# Power.net
KiCad netlist of a schematic drawn in Altium Designer
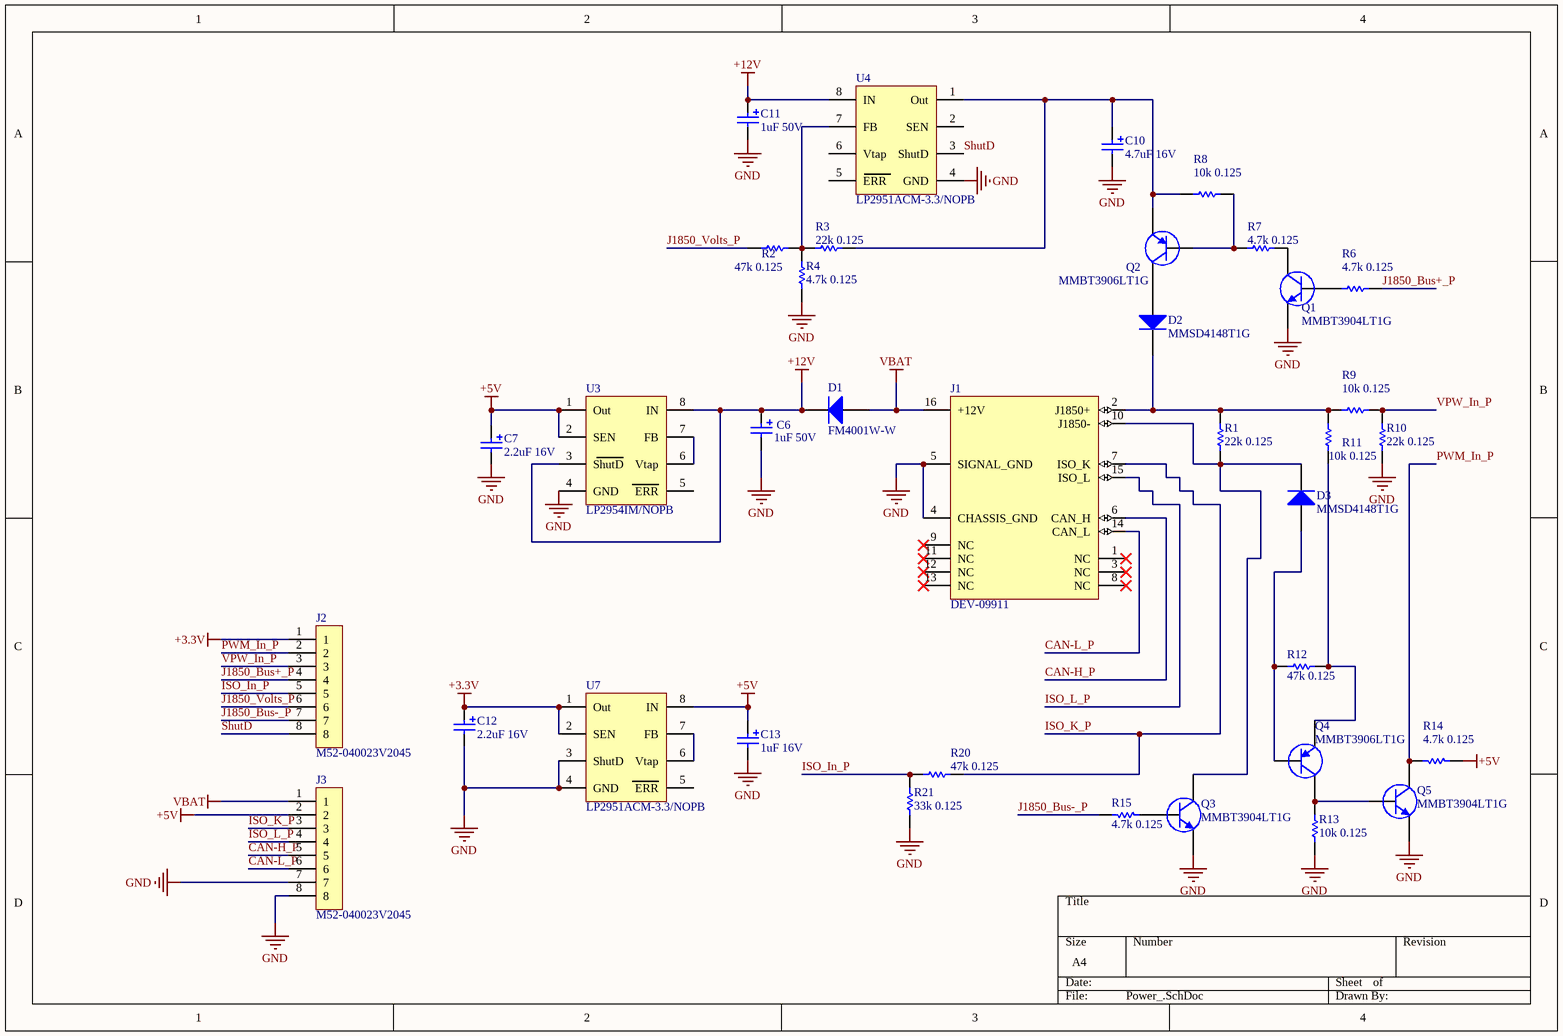
[diagram p0: Power_.SchDoc]

(export (version "E")
  (design (tool "Eeschema 10.0.6"))
  (components
    (comp (ref "C6")
      (value "1uF 50V")
      (footprint "C1005")
      (description "Surface-Mount Electrolitic Tantalum Capacitor, 1uF, 20% Tolerance, 1005 Size, 50V")
      (fields (field (name "PUBLISHER") "Altium Limited"))
      (libsource (lib "OBDII-components") (part "298D105X0050P2T"))
    )
    (comp (ref "C7")
      (value "2.2uF 16V")
      (footprint "C0603")
      (description "Surface-Mount Electrolitic Tantalum Capacitor, 2.2uF, 10% Tolerance, 0603 Size, 16V")
      (fields (field (name "PUBLISHER") "Altium Limited"))
      (libsource (lib "OBDII-components") (part "298D225X0016M2T"))
    )
    (comp (ref "C10")
      (value "4.7uF 16V")
      (footprint "C1005")
      (description "Surface-Mount Electrolitic Tantalum Capacitor, 4.7uF, 20% Tolerance, 1005 Size, 16V")
      (fields (field (name "PUBLISHER") "Altium Limited"))
      (libsource (lib "OBDII-components") (part "298D475X0016P2T"))
    )
    (comp (ref "C11")
      (value "1uF 50V")
      (footprint "C1005")
      (description "Surface-Mount Electrolitic Tantalum Capacitor, 1uF, 20% Tolerance, 1005 Size, 50V")
      (fields (field (name "PUBLISHER") "Altium Limited"))
      (libsource (lib "OBDII-components") (part "298D105X0050P2T"))
    )
    (comp (ref "C12")
      (value "2.2uF 16V")
      (footprint "C0603")
      (description "Surface-Mount Electrolitic Tantalum Capacitor, 2.2uF, 10% Tolerance, 0603 Size, 16V")
      (fields (field (name "PUBLISHER") "Altium Limited"))
      (libsource (lib "OBDII-components") (part "298D225X0016M2T"))
    )
    (comp (ref "C13")
      (value "1uF 16V")
      (footprint "C0603")
      (description "Surface-Mount Electrolitic Tantalum Capacitor, 1uF, 10% Tolerance, 0603 Size, 16V")
      (fields (field (name "PUBLISHER") "Altium Limited"))
      (libsource (lib "OBDII-components") (part "298D105X9016M2T"))
    )
    (comp (ref "D1")
      (value "FM4001W-W")
      (footprint "SMA,2.8mm")
      (description "1 Amp 50V  Rectifier")
      (libsource (lib "OBDII-components") (part "FM4001W-W"))
    )
    (comp (ref "D2")
      (value "MMSD4148T1G")
      (footprint "SOD123")
      (description "High Conductance Fast Diode")
      (fields
        (field (name "MANUFACTURER") "OnSemi")
        (field (name "PUBLISHER") "Vanteon")
        (field (name "APPROVED") "M. Jablonski")
      )
      (libsource (lib "OBDII-components") (part "MMSD4148T1G"))
    )
    (comp (ref "D3")
      (value "MMSD4148T1G")
      (footprint "SOD123")
      (description "High Conductance Fast Diode")
      (fields
        (field (name "MANUFACTURER") "OnSemi")
        (field (name "PUBLISHER") "Vanteon")
        (field (name "APPROVED") "M. Jablonski")
      )
      (libsource (lib "OBDII-components") (part "MMSD4148T1G"))
    )
    (comp (ref "J1")
      (value "DEV-09911")
      (footprint "DEV-09911 - II")
      (description "OBD-II Connector")
      (fields (field (name "MANUFACTURER") "SparkFun Electronics"))
      (libsource (lib "OBDII-components") (part "OBDII_DEV-09911"))
    )
    (comp (ref "J2")
      (value "M52-040023V2045")
      (footprint "M52-040023V2045")
      (description "CONN HEADER .050\" 20POS PCB GOLD")
      (fields (field (name "MANUFACTURER") "Harwin"))
      (libsource (lib "OBDII-components") (part "M52-040023V2045"))
    )
    (comp (ref "J3")
      (value "M52-040023V2045")
      (footprint "M52-040023V2045")
      (description "CONN HEADER .050\" 20POS PCB GOLD")
      (fields (field (name "MANUFACTURER") "Harwin"))
      (libsource (lib "OBDII-components") (part "M52-040023V2045"))
    )
    (comp (ref "Q1")
      (value "MMBT3904LT1G")
      (footprint "SOT23")
      (description "NPN 3904 General Purpose Amplifier")
      (fields
        (field (name "MANUFACTURER") "ON Semiconductor")
        (field (name "PUBLISHER") "Vanteon")
        (field (name "APPROVED") "Yes by Implemenation")
      )
      (libsource (lib "OBDII-components") (part "MMBT3904LT1G"))
    )
    (comp (ref "Q2")
      (value "MMBT3906LT1G")
      (footprint "SOT23")
      (description "PNP 3906 General Purpose Amplifier")
      (fields
        (field (name "MANUFACTURER") "ON Semiconductor")
        (field (name "PUBLISHER") "Vanteon")
        (field (name "APPROVED") "Yes by Implemenation")
      )
      (libsource (lib "OBDII-components") (part "MMBT3906LT1G"))
    )
    (comp (ref "Q3")
      (value "MMBT3904LT1G")
      (footprint "SOT23")
      (description "NPN 3904 General Purpose Amplifier")
      (fields
        (field (name "MANUFACTURER") "ON Semiconductor")
        (field (name "PUBLISHER") "Vanteon")
        (field (name "APPROVED") "Yes by Implemenation")
      )
      (libsource (lib "OBDII-components") (part "MMBT3904LT1G"))
    )
    (comp (ref "Q4")
      (value "MMBT3906LT1G")
      (footprint "SOT23")
      (description "PNP 3906 General Purpose Amplifier")
      (fields
        (field (name "MANUFACTURER") "ON Semiconductor")
        (field (name "PUBLISHER") "Vanteon")
        (field (name "APPROVED") "Yes by Implemenation")
      )
      (libsource (lib "OBDII-components") (part "MMBT3906LT1G"))
    )
    (comp (ref "Q5")
      (value "MMBT3904LT1G")
      (footprint "SOT23")
      (description "NPN 3904 General Purpose Amplifier")
      (fields
        (field (name "MANUFACTURER") "ON Semiconductor")
        (field (name "PUBLISHER") "Vanteon")
        (field (name "APPROVED") "Yes by Implemenation")
      )
      (libsource (lib "OBDII-components") (part "MMBT3904LT1G"))
    )
    (comp (ref "R1")
      (value "22k 0.125")
      (footprint "ERA-0805")
      (description "Rectangular Thick Film Chip Resistor, 22 kOhm, 0.1% Tolerance, 0805 Size, 0.125 W")
      (libsource (lib "OBDII-components") (part "ERA-6AEB223V"))
    )
    (comp (ref "R2")
      (value "47k 0.125")
      (footprint "ERA-0805")
      (description "Rectangular Thick Film Chip Resistor, 47 kOhm, 0.1% Tolerance, 0805 Size, 0.125 W")
      (libsource (lib "OBDII-components") (part "ERA-6AEB473V"))
    )
    (comp (ref "R3")
      (value "22k 0.125")
      (footprint "ERA-0805")
      (description "Rectangular Thick Film Chip Resistor, 22 kOhm, 0.1% Tolerance, 0805 Size, 0.125 W")
      (libsource (lib "OBDII-components") (part "ERA-6AEB223V"))
    )
    (comp (ref "R4")
      (value "4.7k 0.125")
      (footprint "ERA-0805")
      (description "Rectangular Thick Film Chip Resistor, 4.7 kOhm, 0.1% Tolerance, 0805 Size, 0.125 W")
      (libsource (lib "OBDII-components") (part "ERA-6AEB472V"))
    )
    (comp (ref "R6")
      (value "4.7k 0.125")
      (footprint "ERA-0805")
      (description "Rectangular Thick Film Chip Resistor, 4.7 kOhm, 0.1% Tolerance, 0805 Size, 0.125 W")
      (libsource (lib "OBDII-components") (part "ERA-6AEB472V"))
    )
    (comp (ref "R7")
      (value "4.7k 0.125")
      (footprint "ERA-0805")
      (description "Rectangular Thick Film Chip Resistor, 4.7 kOhm, 0.1% Tolerance, 0805 Size, 0.125 W")
      (libsource (lib "OBDII-components") (part "ERA-6AEB472V"))
    )
    (comp (ref "R8")
      (value "10k 0.125")
      (footprint "ERA-0805")
      (description "Rectangular Thick Film Chip Resistor, 10 kOhm, 0.1% Tolerance, 0805 Size, 0.125 W")
      (libsource (lib "OBDII-components") (part "ERA-6AEB103V"))
    )
    (comp (ref "R9")
      (value "10k 0.125")
      (footprint "ERA-0805")
      (description "Rectangular Thick Film Chip Resistor, 10 kOhm, 0.1% Tolerance, 0805 Size, 0.125 W")
      (libsource (lib "OBDII-components") (part "ERA-6AEB103V"))
    )
    (comp (ref "R10")
      (value "22k 0.125")
      (footprint "ERA-0805")
      (description "Rectangular Thick Film Chip Resistor, 22 kOhm, 0.1% Tolerance, 0805 Size, 0.125 W")
      (libsource (lib "OBDII-components") (part "ERA-6AEB223V"))
    )
    (comp (ref "R11")
      (value "10k 0.125")
      (footprint "ERA-0805")
      (description "Rectangular Thick Film Chip Resistor, 10 kOhm, 0.1% Tolerance, 0805 Size, 0.125 W")
      (libsource (lib "OBDII-components") (part "ERA-6AEB103V"))
    )
    (comp (ref "R12")
      (value "47k 0.125")
      (footprint "ERA-0805")
      (description "Rectangular Thick Film Chip Resistor, 47 kOhm, 0.1% Tolerance, 0805 Size, 0.125 W")
      (libsource (lib "OBDII-components") (part "ERA-6AEB473V"))
    )
    (comp (ref "R13")
      (value "10k 0.125")
      (footprint "ERA-0805")
      (description "Rectangular Thick Film Chip Resistor, 10 kOhm, 0.1% Tolerance, 0805 Size, 0.125 W")
      (libsource (lib "OBDII-components") (part "ERA-6AEB103V"))
    )
    (comp (ref "R14")
      (value "4.7k 0.125")
      (footprint "ERA-0805")
      (description "Rectangular Thick Film Chip Resistor, 4.7 kOhm, 0.1% Tolerance, 0805 Size, 0.125 W")
      (libsource (lib "OBDII-components") (part "ERA-6AEB472V"))
    )
    (comp (ref "R15")
      (value "4.7k 0.125")
      (footprint "ERA-0805")
      (description "Rectangular Thick Film Chip Resistor, 4.7 kOhm, 0.1% Tolerance, 0805 Size, 0.125 W")
      (libsource (lib "OBDII-components") (part "ERA-6AEB472V"))
    )
    (comp (ref "R20")
      (value "47k 0.125")
      (footprint "ERA-0805")
      (description "Rectangular Thick Film Chip Resistor, 47 kOhm, 0.1% Tolerance, 0805 Size, 0.125 W")
      (libsource (lib "OBDII-components") (part "ERA-6AEB473V"))
    )
    (comp (ref "R21")
      (value "33k 0.125")
      (footprint "ERA-0805")
      (description "Rectangular Thick Film Chip Resistor, 33 kOhm, 0.1% Tolerance, 0805 Size, 0.125 W")
      (libsource (lib "OBDII-components") (part "ERA-6AEB333V"))
    )
    (comp (ref "U3")
      (value "LP2954IM/NOPB")
      (footprint "SOIC8N")
      (description "LDO Voltage Regulators  1.2V-29V 0.25A SOIC8")
      (fields
        (field (name "MANUFACTURER") "Texas Instruments")
        (field (name "APPROVED") "Yes by Implementation")
      )
      (libsource (lib "OBDII-components") (part "LP2954IM/NOPB"))
    )
    (comp (ref "U4")
      (value "LP2951ACM-3.3/NOPB")
      (footprint "SOIC8N")
      (description "LDO Voltage Regulators  1.2V-37V 0.1A SOIC8")
      (fields
        (field (name "MANUFACTURER") "Texas Instruments")
        (field (name "APPROVED") "Yes by Implementation")
      )
      (libsource (lib "OBDII-components") (part "LP2951ACM-3.3/NOPB"))
    )
    (comp (ref "U7")
      (value "LP2951ACM-3.3/NOPB")
      (footprint "SOIC8N")
      (description "LDO Voltage Regulators  1.2V-37V 0.1A SOIC8")
      (fields
        (field (name "MANUFACTURER") "Texas Instruments")
        (field (name "APPROVED") "Yes by Implementation")
      )
      (libsource (lib "") (part "LP2951ACM-3.3/NOPB_1"))
    )
  )
  (nets
    (net (code "1") (name "+3.3V") (class "Default")
      (node (ref "C12") (pin "1") (pinfunction "1_1") (pintype "passive"))
      (node (ref "J2") (pin "1") (pinfunction "1_1") (pintype "passive"))
      (node (ref "U7") (pin "1") (pinfunction "Out_1") (pintype "power_in"))
      (node (ref "U7") (pin "2") (pinfunction "SEN_2") (pintype "passive"))
    )
    (net (code "2") (name "+5V") (class "Default")
      (node (ref "C13") (pin "1") (pinfunction "1_1") (pintype "passive"))
      (node (ref "C7") (pin "1") (pinfunction "1_1") (pintype "passive"))
      (node (ref "J3") (pin "2") (pinfunction "2_2") (pintype "passive"))
      (node (ref "R14") (pin "1") (pinfunction "1_1") (pintype "passive"))
      (node (ref "U3") (pin "1") (pinfunction "Out_1") (pintype "power_in"))
      (node (ref "U3") (pin "2") (pinfunction "SEN_2") (pintype "passive"))
      (node (ref "U7") (pin "8") (pinfunction "IN_8") (pintype "passive"))
    )
    (net (code "3") (name "+12V") (class "Default")
      (node (ref "C11") (pin "1") (pinfunction "1_1") (pintype "passive"))
      (node (ref "C6") (pin "1") (pinfunction "1_1") (pintype "passive"))
      (node (ref "D1") (pin "2") (pinfunction "K_2") (pintype "passive"))
      (node (ref "U3") (pin "3") (pinfunction "ShutD_3") (pintype "passive"))
      (node (ref "U3") (pin "8") (pinfunction "IN_8") (pintype "passive"))
      (node (ref "U4") (pin "8") (pinfunction "IN_8") (pintype "passive"))
    )
    (net (code "4") (name "/CAN-H_P") (class "Default")
      (node (ref "J1") (pin "6") (pinfunction "CAN_H_6") (pintype "bidirectional"))
      (node (ref "J3") (pin "5") (pinfunction "5_5") (pintype "passive"))
    )
    (net (code "5") (name "/CAN-L_P") (class "Default")
      (node (ref "J1") (pin "14") (pinfunction "CAN_L_14") (pintype "bidirectional"))
      (node (ref "J3") (pin "6") (pinfunction "6_6") (pintype "passive"))
    )
    (net (code "6") (name "/ISO_In_P") (class "Default")
      (node (ref "J2") (pin "5") (pinfunction "5_5") (pintype "passive"))
      (node (ref "R20") (pin "1") (pinfunction "1_1") (pintype "passive"))
      (node (ref "R21") (pin "2") (pinfunction "2_2") (pintype "passive"))
    )
    (net (code "7") (name "/ISO_K_P") (class "Default")
      (node (ref "J1") (pin "7") (pinfunction "ISO_K_7") (pintype "bidirectional"))
      (node (ref "J3") (pin "3") (pinfunction "3_3") (pintype "passive"))
      (node (ref "R20") (pin "2") (pinfunction "2_2") (pintype "passive"))
    )
    (net (code "8") (name "/ISO_L_P") (class "Default")
      (node (ref "J1") (pin "15") (pinfunction "ISO_L_15") (pintype "bidirectional"))
      (node (ref "J3") (pin "4") (pinfunction "4_4") (pintype "passive"))
    )
    (net (code "9") (name "/J1850_Bus+_P") (class "Default")
      (node (ref "J2") (pin "4") (pinfunction "4_4") (pintype "passive"))
      (node (ref "R6") (pin "2") (pinfunction "2_2") (pintype "passive"))
    )
    (net (code "10") (name "/J1850_Bus-_P") (class "Default")
      (node (ref "J2") (pin "7") (pinfunction "7_7") (pintype "passive"))
      (node (ref "R15") (pin "2") (pinfunction "2_2") (pintype "passive"))
    )
    (net (code "11") (name "/J1850_Volts_P") (class "Default")
      (node (ref "J2") (pin "6") (pinfunction "6_6") (pintype "passive"))
      (node (ref "R2") (pin "1") (pinfunction "1_1") (pintype "passive"))
    )
    (net (code "12") (name "/PWM_In_P") (class "Default")
      (node (ref "J2") (pin "2") (pinfunction "2_2") (pintype "passive"))
      (node (ref "Q5") (pin "3") (pinfunction "C_3") (pintype "passive"))
      (node (ref "R14") (pin "2") (pinfunction "2_2") (pintype "passive"))
    )
    (net (code "13") (name "/ShutD") (class "Default")
      (node (ref "J2") (pin "8") (pinfunction "8_8") (pintype "passive"))
      (node (ref "U4") (pin "3") (pinfunction "ShutD_3") (pintype "passive"))
    )
    (net (code "14") (name "/VPW_In_P") (class "Default")
      (node (ref "J2") (pin "3") (pinfunction "3_3") (pintype "passive"))
      (node (ref "R10") (pin "2") (pinfunction "2_2") (pintype "passive"))
      (node (ref "R9") (pin "1") (pinfunction "1_1") (pintype "passive"))
    )
    (net (code "15") (name "GND") (class "Default")
      (node (ref "C10") (pin "2") (pinfunction "2_2") (pintype "passive"))
      (node (ref "C11") (pin "2") (pinfunction "2_2") (pintype "passive"))
      (node (ref "C12") (pin "2") (pinfunction "2_2") (pintype "passive"))
      (node (ref "C13") (pin "2") (pinfunction "2_2") (pintype "passive"))
      (node (ref "C6") (pin "2") (pinfunction "2_2") (pintype "passive"))
      (node (ref "C7") (pin "2") (pinfunction "2_2") (pintype "passive"))
      (node (ref "J1") (pin "4") (pinfunction "CHASSIS_GND_4") (pintype "power_in"))
      (node (ref "J1") (pin "5") (pinfunction "SIGNAL_GND_5") (pintype "power_in"))
      (node (ref "J3") (pin "7") (pinfunction "7_7") (pintype "passive"))
      (node (ref "J3") (pin "8") (pinfunction "8_8") (pintype "passive"))
      (node (ref "Q1") (pin "2") (pinfunction "E_2") (pintype "passive"))
      (node (ref "Q3") (pin "2") (pinfunction "E_2") (pintype "passive"))
      (node (ref "Q5") (pin "2") (pinfunction "E_2") (pintype "passive"))
      (node (ref "R10") (pin "1") (pinfunction "1_1") (pintype "passive"))
      (node (ref "R13") (pin "2") (pinfunction "2_2") (pintype "passive"))
      (node (ref "R21") (pin "1") (pinfunction "1_1") (pintype "passive"))
      (node (ref "R4") (pin "1") (pinfunction "1_1") (pintype "passive"))
      (node (ref "U3") (pin "4") (pinfunction "GND_4") (pintype "power_in"))
      (node (ref "U4") (pin "4") (pinfunction "GND_4") (pintype "power_in"))
      (node (ref "U7") (pin "3") (pinfunction "ShutD_3") (pintype "passive"))
      (node (ref "U7") (pin "4") (pinfunction "GND_4") (pintype "power_in"))
    )
    (net (code "16") (name "Net-(D2-A)") (class "Default")
      (node (ref "D2") (pin "1") (pinfunction "A_1") (pintype "passive"))
      (node (ref "Q2") (pin "3") (pinfunction "C_3") (pintype "passive"))
    )
    (net (code "17") (name "Net-(D2-C)") (class "Default")
      (node (ref "D2") (pin "2") (pinfunction "C_2") (pintype "passive"))
      (node (ref "J1") (pin "2") (pinfunction "J1850+_2") (pintype "bidirectional"))
      (node (ref "R1") (pin "2") (pinfunction "2_2") (pintype "passive"))
      (node (ref "R11") (pin "1") (pinfunction "1_1") (pintype "passive"))
      (node (ref "R9") (pin "2") (pinfunction "2_2") (pintype "passive"))
    )
    (net (code "18") (name "Net-(D3-A)") (class "Default")
      (node (ref "D3") (pin "1") (pinfunction "A_1") (pintype "passive"))
      (node (ref "Q4") (pin "1") (pinfunction "B_1") (pintype "passive"))
      (node (ref "R12") (pin "1") (pinfunction "1_1") (pintype "passive"))
    )
    (net (code "19") (name "Net-(D3-C)") (class "Default")
      (node (ref "D3") (pin "2") (pinfunction "C_2") (pintype "passive"))
      (node (ref "J1") (pin "10") (pinfunction "J1850-_10") (pintype "bidirectional"))
      (node (ref "Q3") (pin "3") (pinfunction "C_3") (pintype "passive"))
      (node (ref "R1") (pin "1") (pinfunction "1_1") (pintype "passive"))
    )
    (net (code "20") (name "Net-(Q1-B)") (class "Default")
      (node (ref "Q1") (pin "1") (pinfunction "B_1") (pintype "passive"))
      (node (ref "R6") (pin "1") (pinfunction "1_1") (pintype "passive"))
    )
    (net (code "21") (name "Net-(Q1-C)") (class "Default")
      (node (ref "Q1") (pin "3") (pinfunction "C_3") (pintype "passive"))
      (node (ref "R7") (pin "2") (pinfunction "2_2") (pintype "passive"))
    )
    (net (code "22") (name "Net-(Q2-B)") (class "Default")
      (node (ref "Q2") (pin "1") (pinfunction "B_1") (pintype "passive"))
      (node (ref "R7") (pin "1") (pinfunction "1_1") (pintype "passive"))
      (node (ref "R8") (pin "1") (pinfunction "1_1") (pintype "passive"))
    )
    (net (code "23") (name "Net-(Q2-E)") (class "Default")
      (node (ref "C10") (pin "1") (pinfunction "1_1") (pintype "passive"))
      (node (ref "Q2") (pin "2") (pinfunction "E_2") (pintype "passive"))
      (node (ref "R3") (pin "2") (pinfunction "2_2") (pintype "passive"))
      (node (ref "R8") (pin "2") (pinfunction "2_2") (pintype "passive"))
      (node (ref "U4") (pin "1") (pinfunction "Out_1") (pintype "power_in"))
    )
    (net (code "24") (name "Net-(Q3-B)") (class "Default")
      (node (ref "Q3") (pin "1") (pinfunction "B_1") (pintype "passive"))
      (node (ref "R15") (pin "1") (pinfunction "1_1") (pintype "passive"))
    )
    (net (code "25") (name "Net-(Q4-C)") (class "Default")
      (node (ref "Q4") (pin "3") (pinfunction "C_3") (pintype "passive"))
      (node (ref "Q5") (pin "1") (pinfunction "B_1") (pintype "passive"))
      (node (ref "R13") (pin "1") (pinfunction "1_1") (pintype "passive"))
    )
    (net (code "26") (name "Net-(Q4-E)") (class "Default")
      (node (ref "Q4") (pin "2") (pinfunction "E_2") (pintype "passive"))
      (node (ref "R11") (pin "2") (pinfunction "2_2") (pintype "passive"))
      (node (ref "R12") (pin "2") (pinfunction "2_2") (pintype "passive"))
    )
    (net (code "27") (name "Net-(U3-FB)") (class "Default")
      (node (ref "U3") (pin "6") (pinfunction "Vtap_6") (pintype "passive"))
      (node (ref "U3") (pin "7") (pinfunction "FB_7") (pintype "passive"))
    )
    (net (code "28") (name "Net-(U4-FB)") (class "Default")
      (node (ref "R2") (pin "2") (pinfunction "2_2") (pintype "passive"))
      (node (ref "R3") (pin "1") (pinfunction "1_1") (pintype "passive"))
      (node (ref "R4") (pin "2") (pinfunction "2_2") (pintype "passive"))
      (node (ref "U4") (pin "7") (pinfunction "FB_7") (pintype "passive"))
    )
    (net (code "29") (name "Net-(U7-FB)") (class "Default")
      (node (ref "U7") (pin "6") (pinfunction "Vtap_6") (pintype "passive"))
      (node (ref "U7") (pin "7") (pinfunction "FB_7") (pintype "passive"))
    )
    (net (code "30") (name "VBAT") (class "Default")
      (node (ref "D1") (pin "1") (pinfunction "A_1") (pintype "passive"))
      (node (ref "J1") (pin "16") (pinfunction "+12V_16") (pintype "power_in"))
      (node (ref "J3") (pin "1") (pinfunction "1_1") (pintype "passive"))
    )
    (net (code "31") (name "unconnected-(J1-NC-Pad1)") (class "Default")
      (node (ref "J1") (pin "1") (pinfunction "NC_1") (pintype "passive+no_connect"))
    )
    (net (code "32") (name "unconnected-(J1-NC-Pad3)") (class "Default")
      (node (ref "J1") (pin "3") (pinfunction "NC_3") (pintype "passive+no_connect"))
    )
    (net (code "33") (name "unconnected-(J1-NC-Pad8)") (class "Default")
      (node (ref "J1") (pin "8") (pinfunction "NC_8") (pintype "passive+no_connect"))
    )
    (net (code "34") (name "unconnected-(J1-NC-Pad9)") (class "Default")
      (node (ref "J1") (pin "9") (pinfunction "NC_9") (pintype "passive+no_connect"))
    )
    (net (code "35") (name "unconnected-(J1-NC-Pad11)") (class "Default")
      (node (ref "J1") (pin "11") (pinfunction "NC_11") (pintype "passive+no_connect"))
    )
    (net (code "36") (name "unconnected-(J1-NC-Pad12)") (class "Default")
      (node (ref "J1") (pin "12") (pinfunction "NC_12") (pintype "passive+no_connect"))
    )
    (net (code "37") (name "unconnected-(J1-NC-Pad13)") (class "Default")
      (node (ref "J1") (pin "13") (pinfunction "NC_13") (pintype "passive+no_connect"))
    )
    (net (code "38") (name "unconnected-(U3-ERR-Pad5)") (class "Default")
      (node (ref "U3") (pin "5") (pinfunction "ERR_5") (pintype "passive"))
    )
    (net (code "39") (name "unconnected-(U4-ERR-Pad5)") (class "Default")
      (node (ref "U4") (pin "5") (pinfunction "ERR_5") (pintype "passive"))
    )
    (net (code "40") (name "unconnected-(U4-SEN-Pad2)") (class "Default")
      (node (ref "U4") (pin "2") (pinfunction "SEN_2") (pintype "passive"))
    )
    (net (code "41") (name "unconnected-(U4-Vtap-Pad6)") (class "Default")
      (node (ref "U4") (pin "6") (pinfunction "Vtap_6") (pintype "passive"))
    )
    (net (code "42") (name "unconnected-(U7-ERR-Pad5)") (class "Default")
      (node (ref "U7") (pin "5") (pinfunction "ERR_5") (pintype "passive"))
    )
  )
)
